# 131210_AriloRX_0_0.net
KiCad netlist of a schematic drawn in EAGLE
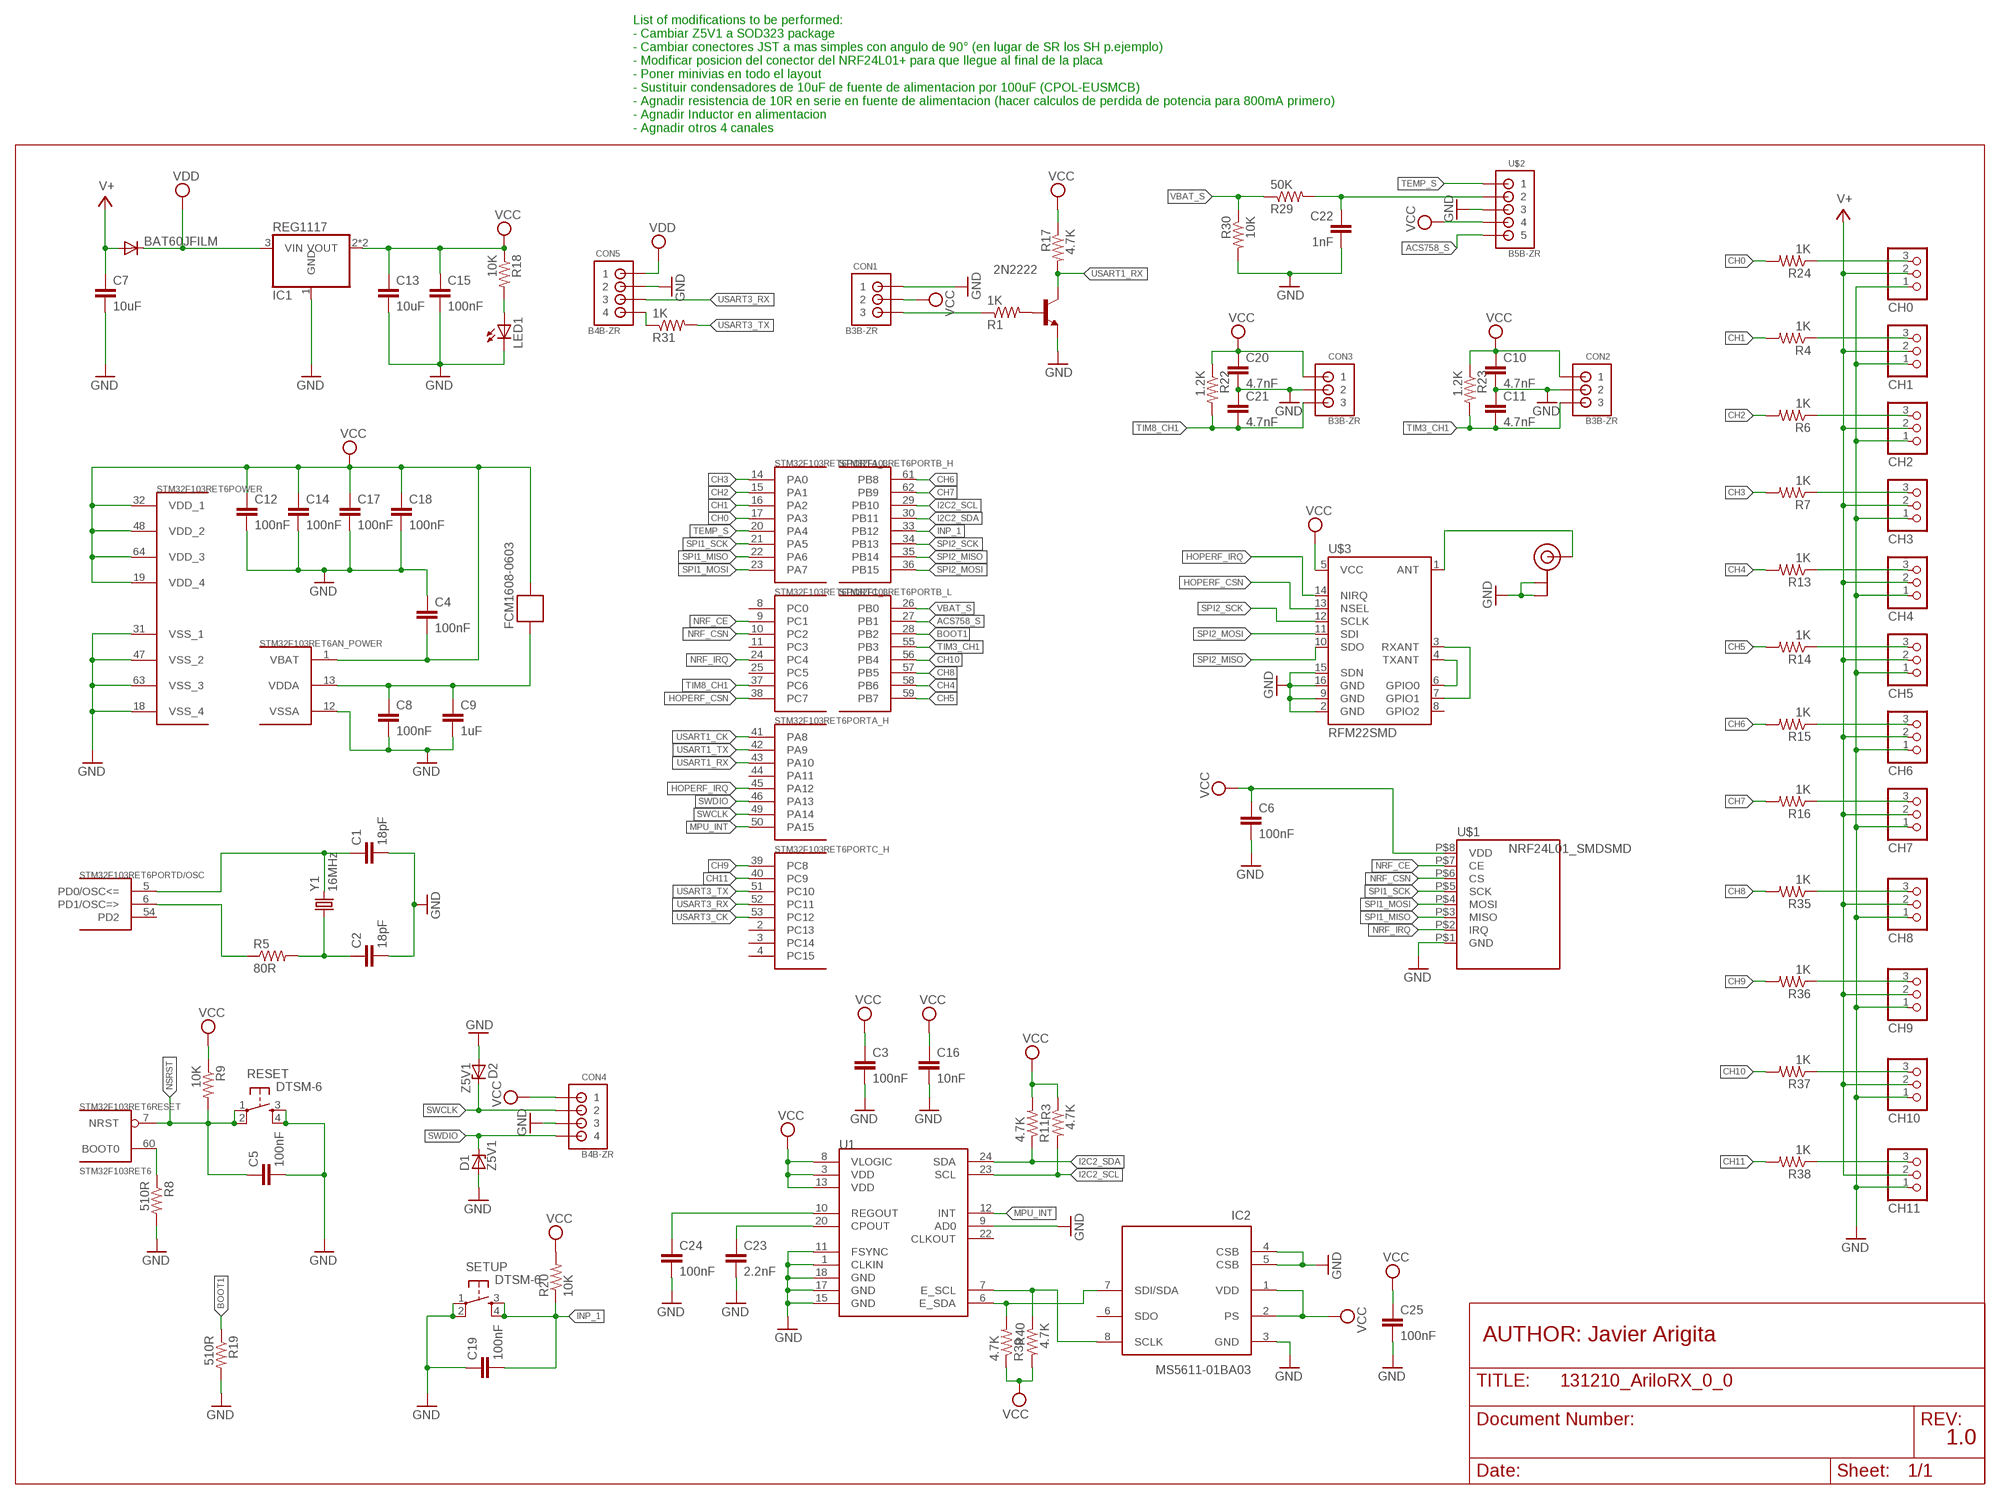
[diagram p0: schematic, sheet 1]

(export (version "E")
  (design (tool "Eeschema 10.0.6"))
  (components
    (comp (ref "2N2222")
      (value "MMBT2222ALT1-NPN-SOT23-BEC")
      (footprint "eagle-import:SOT23-BEC")
      (libsource (lib "eagle-import") (part "-NPN-SOT23-BECMMBT2222ALT1"))
    )
    (comp (ref "BAT60JFILM")
      (value "DIODE-SOD323-R")
      (footprint "eagle-import:SOD323-R")
      (libsource (lib "eagle-import") (part "DIODE-SOD323-R"))
    )
    (comp (ref "C1")
      (value "18pF")
      (footprint "eagle-import:C0805")
      (libsource (lib "eagle-import") (part "C-EUC0805"))
    )
    (comp (ref "C2")
      (value "18pF")
      (footprint "eagle-import:C0805")
      (libsource (lib "eagle-import") (part "C-EUC0805"))
    )
    (comp (ref "C3")
      (value "100nF")
      (footprint "eagle-import:C0805")
      (libsource (lib "eagle-import") (part "C-EUC0805"))
    )
    (comp (ref "C4")
      (value "100nF")
      (footprint "eagle-import:C0805")
      (libsource (lib "eagle-import") (part "C-EUC0805"))
    )
    (comp (ref "C5")
      (value "100nF")
      (footprint "eagle-import:C0805")
      (libsource (lib "eagle-import") (part "C-EUC0805"))
    )
    (comp (ref "C6")
      (value "100nF")
      (footprint "eagle-import:C0805")
      (libsource (lib "eagle-import") (part "C-EUC0805"))
    )
    (comp (ref "C7")
      (value "10uF")
      (footprint "eagle-import:C3216")
      (libsource (lib "eagle-import") (part "resistor_C-EUC3216"))
    )
    (comp (ref "C8")
      (value "100nF")
      (footprint "eagle-import:C0805")
      (libsource (lib "eagle-import") (part "C-EUC0805"))
    )
    (comp (ref "C9")
      (value "1uF")
      (footprint "eagle-import:C3216")
      (libsource (lib "eagle-import") (part "resistor_C-EUC3216"))
    )
    (comp (ref "C10")
      (value "4.7nF")
      (footprint "eagle-import:C0805")
      (libsource (lib "eagle-import") (part "C-EUC0805"))
    )
    (comp (ref "C11")
      (value "4.7nF")
      (footprint "eagle-import:C0805")
      (libsource (lib "eagle-import") (part "C-EUC0805"))
    )
    (comp (ref "C12")
      (value "100nF")
      (footprint "eagle-import:C0805")
      (libsource (lib "eagle-import") (part "C-EUC0805"))
    )
    (comp (ref "C13")
      (value "10uF")
      (footprint "eagle-import:C3216")
      (libsource (lib "eagle-import") (part "resistor_C-EUC3216"))
    )
    (comp (ref "C14")
      (value "100nF")
      (footprint "eagle-import:C0805")
      (libsource (lib "eagle-import") (part "C-EUC0805"))
    )
    (comp (ref "C15")
      (value "100nF")
      (footprint "eagle-import:C0805")
      (libsource (lib "eagle-import") (part "C-EUC0805"))
    )
    (comp (ref "C16")
      (value "10nF")
      (footprint "eagle-import:C0805")
      (libsource (lib "eagle-import") (part "C-EUC0805"))
    )
    (comp (ref "C17")
      (value "100nF")
      (footprint "eagle-import:C0805")
      (libsource (lib "eagle-import") (part "C-EUC0805"))
    )
    (comp (ref "C18")
      (value "100nF")
      (footprint "eagle-import:C0805")
      (libsource (lib "eagle-import") (part "C-EUC0805"))
    )
    (comp (ref "C19")
      (value "100nF")
      (footprint "eagle-import:C0805")
      (libsource (lib "eagle-import") (part "C-EUC0805"))
    )
    (comp (ref "C20")
      (value "4.7nF")
      (footprint "eagle-import:C0805")
      (libsource (lib "eagle-import") (part "C-EUC0805"))
    )
    (comp (ref "C21")
      (value "4.7nF")
      (footprint "eagle-import:C0805")
      (libsource (lib "eagle-import") (part "C-EUC0805"))
    )
    (comp (ref "C22")
      (value "1nF")
      (footprint "eagle-import:C0805")
      (libsource (lib "eagle-import") (part "C-EUC0805"))
    )
    (comp (ref "C23")
      (value "2.2nF")
      (footprint "eagle-import:C0805")
      (libsource (lib "eagle-import") (part "C-EUC0805"))
    )
    (comp (ref "C24")
      (value "100nF")
      (footprint "eagle-import:C0805")
      (libsource (lib "eagle-import") (part "C-EUC0805"))
    )
    (comp (ref "C25")
      (value "100nF")
      (footprint "eagle-import:C0805")
      (libsource (lib "eagle-import") (part "C-EUC0805"))
    )
    (comp (ref "CH0")
      (value "PINHD-1X3")
      (footprint "eagle-import:1X03")
      (libsource (lib "eagle-import") (part "PINHD-1X3"))
    )
    (comp (ref "CH1")
      (value "PINHD-1X3")
      (footprint "eagle-import:1X03")
      (libsource (lib "eagle-import") (part "PINHD-1X3"))
    )
    (comp (ref "CH2")
      (value "PINHD-1X3")
      (footprint "eagle-import:1X03")
      (libsource (lib "eagle-import") (part "PINHD-1X3"))
    )
    (comp (ref "CH3")
      (value "PINHD-1X3")
      (footprint "eagle-import:1X03")
      (libsource (lib "eagle-import") (part "PINHD-1X3"))
    )
    (comp (ref "CH4")
      (value "PINHD-1X3")
      (footprint "eagle-import:1X03")
      (libsource (lib "eagle-import") (part "PINHD-1X3"))
    )
    (comp (ref "CH5")
      (value "PINHD-1X3")
      (footprint "eagle-import:1X03")
      (libsource (lib "eagle-import") (part "PINHD-1X3"))
    )
    (comp (ref "CH6")
      (value "PINHD-1X3")
      (footprint "eagle-import:1X03")
      (libsource (lib "eagle-import") (part "PINHD-1X3"))
    )
    (comp (ref "CH7")
      (value "PINHD-1X3")
      (footprint "eagle-import:1X03")
      (libsource (lib "eagle-import") (part "PINHD-1X3"))
    )
    (comp (ref "CH8")
      (value "PINHD-1X3")
      (footprint "eagle-import:1X03")
      (libsource (lib "eagle-import") (part "PINHD-1X3"))
    )
    (comp (ref "CH9")
      (value "PINHD-1X3")
      (footprint "eagle-import:1X03")
      (libsource (lib "eagle-import") (part "PINHD-1X3"))
    )
    (comp (ref "CH10")
      (value "PINHD-1X3")
      (footprint "eagle-import:1X03")
      (libsource (lib "eagle-import") (part "PINHD-1X3"))
    )
    (comp (ref "CH11")
      (value "PINHD-1X3")
      (footprint "eagle-import:1X03")
      (libsource (lib "eagle-import") (part "PINHD-1X3"))
    )
    (comp (ref "CON1")
      (value "B3B-ZR")
      (footprint "eagle-import:B3B-ZR")
      (libsource (lib "eagle-import") (part "B3B-ZR"))
    )
    (comp (ref "CON2")
      (value "B3B-ZR")
      (footprint "eagle-import:B3B-ZR")
      (libsource (lib "eagle-import") (part "B3B-ZR"))
    )
    (comp (ref "CON3")
      (value "B3B-ZR")
      (footprint "eagle-import:B3B-ZR")
      (libsource (lib "eagle-import") (part "B3B-ZR"))
    )
    (comp (ref "CON4")
      (value "B4B-ZR")
      (footprint "eagle-import:B4B-ZR")
      (libsource (lib "eagle-import") (part "B4B-ZR"))
    )
    (comp (ref "CON5")
      (value "B4B-ZR")
      (footprint "eagle-import:B4B-ZR")
      (libsource (lib "eagle-import") (part "B4B-ZR"))
    )
    (comp (ref "D1")
      (value "Z5V1")
      (footprint "eagle-import:SOD80C")
      (libsource (lib "eagle-import") (part "ZENER-DIODESOD80C"))
    )
    (comp (ref "D2")
      (value "Z5V1")
      (footprint "eagle-import:SOD80C")
      (libsource (lib "eagle-import") (part "ZENER-DIODESOD80C"))
    )
    (comp (ref "FCM1608-0603")
      (value "FERRITE-BEAD")
      (footprint "eagle-import:R0603")
      (libsource (lib "eagle-import") (part "FERRITE-BEAD"))
    )
    (comp (ref "IC1")
      (value "REG1117")
      (footprint "eagle-import:SOT223")
      (libsource (lib "eagle-import") (part "REG1117"))
    )
    (comp (ref "IC2")
      (value "MS5611-01BA03")
      (footprint "eagle-import:SON125P300X500X100-8N")
      (libsource (lib "eagle-import") (part "MS5611-01BA03"))
    )
    (comp (ref "LED1")
      (value "LED0805")
      (footprint "eagle-import:CHIPLED_0805")
      (libsource (lib "eagle-import") (part "LED0805"))
    )
    (comp (ref "R1")
      (value "1K")
      (footprint "eagle-import:R0805")
      (libsource (lib "eagle-import") (part "RESISTOR0805"))
    )
    (comp (ref "R3")
      (value "4.7K")
      (footprint "eagle-import:R0805")
      (libsource (lib "eagle-import") (part "RESISTOR0805"))
    )
    (comp (ref "R4")
      (value "1K")
      (footprint "eagle-import:R0805")
      (libsource (lib "eagle-import") (part "RESISTOR0805"))
    )
    (comp (ref "R5")
      (value "80R")
      (footprint "eagle-import:R0805")
      (libsource (lib "eagle-import") (part "RESISTOR0805"))
    )
    (comp (ref "R6")
      (value "1K")
      (footprint "eagle-import:R0805")
      (libsource (lib "eagle-import") (part "RESISTOR0805"))
    )
    (comp (ref "R7")
      (value "1K")
      (footprint "eagle-import:R0805")
      (libsource (lib "eagle-import") (part "RESISTOR0805"))
    )
    (comp (ref "R8")
      (value "510R")
      (footprint "eagle-import:R0805")
      (libsource (lib "eagle-import") (part "RESISTOR0805"))
    )
    (comp (ref "R9")
      (value "10K")
      (footprint "eagle-import:R0805")
      (libsource (lib "eagle-import") (part "RESISTOR0805"))
    )
    (comp (ref "R11")
      (value "4.7K")
      (footprint "eagle-import:R0805")
      (libsource (lib "eagle-import") (part "RESISTOR0805"))
    )
    (comp (ref "R13")
      (value "1K")
      (footprint "eagle-import:R0805")
      (libsource (lib "eagle-import") (part "RESISTOR0805"))
    )
    (comp (ref "R14")
      (value "1K")
      (footprint "eagle-import:R0805")
      (libsource (lib "eagle-import") (part "RESISTOR0805"))
    )
    (comp (ref "R15")
      (value "1K")
      (footprint "eagle-import:R0805")
      (libsource (lib "eagle-import") (part "RESISTOR0805"))
    )
    (comp (ref "R16")
      (value "1K")
      (footprint "eagle-import:R0805")
      (libsource (lib "eagle-import") (part "RESISTOR0805"))
    )
    (comp (ref "R17")
      (value "4.7K")
      (footprint "eagle-import:R0805")
      (libsource (lib "eagle-import") (part "RESISTOR0805"))
    )
    (comp (ref "R18")
      (value "10K")
      (footprint "eagle-import:R0805")
      (libsource (lib "eagle-import") (part "RESISTOR0805"))
    )
    (comp (ref "R19")
      (value "510R")
      (footprint "eagle-import:R0805")
      (libsource (lib "eagle-import") (part "RESISTOR0805"))
    )
    (comp (ref "R20")
      (value "10K")
      (footprint "eagle-import:R0805")
      (libsource (lib "eagle-import") (part "RESISTOR0805"))
    )
    (comp (ref "R22")
      (value "1.2K")
      (footprint "eagle-import:R0805")
      (libsource (lib "eagle-import") (part "RESISTOR0805"))
    )
    (comp (ref "R23")
      (value "1.2K")
      (footprint "eagle-import:R0805")
      (libsource (lib "eagle-import") (part "RESISTOR0805"))
    )
    (comp (ref "R24")
      (value "1K")
      (footprint "eagle-import:R0805")
      (libsource (lib "eagle-import") (part "RESISTOR0805"))
    )
    (comp (ref "R29")
      (value "50K")
      (footprint "eagle-import:R0805")
      (libsource (lib "eagle-import") (part "RESISTOR0805"))
    )
    (comp (ref "R30")
      (value "10K")
      (footprint "eagle-import:R0805")
      (libsource (lib "eagle-import") (part "RESISTOR0805"))
    )
    (comp (ref "R31")
      (value "1K")
      (footprint "eagle-import:R0805")
      (libsource (lib "eagle-import") (part "RESISTOR0805"))
    )
    (comp (ref "R35")
      (value "1K")
      (footprint "eagle-import:R0805")
      (libsource (lib "eagle-import") (part "RESISTOR0805"))
    )
    (comp (ref "R36")
      (value "1K")
      (footprint "eagle-import:R0805")
      (libsource (lib "eagle-import") (part "RESISTOR0805"))
    )
    (comp (ref "R37")
      (value "1K")
      (footprint "eagle-import:R0805")
      (libsource (lib "eagle-import") (part "RESISTOR0805"))
    )
    (comp (ref "R38")
      (value "1K")
      (footprint "eagle-import:R0805")
      (libsource (lib "eagle-import") (part "RESISTOR0805"))
    )
    (comp (ref "R39")
      (value "4.7K")
      (footprint "eagle-import:R0805")
      (libsource (lib "eagle-import") (part "RESISTOR0805"))
    )
    (comp (ref "R40")
      (value "4.7K")
      (footprint "eagle-import:R0805")
      (libsource (lib "eagle-import") (part "RESISTOR0805"))
    )
    (comp (ref "RESET")
      (value "DTSM-6")
      (footprint "eagle-import:DTSM-6")
      (libsource (lib "eagle-import") (part "DTSM-6"))
    )
    (comp (ref "SETUP")
      (value "DTSM-6")
      (footprint "eagle-import:DTSM-6")
      (libsource (lib "eagle-import") (part "DTSM-6"))
    )
    (comp (ref "STM32F103RET6")
      (value "STM32F103RET6")
      (footprint "eagle-import:TQFP64")
      (libsource (lib "eagle-import") (part "STM32F10XRXT6"))
    )
    (comp (ref "U$1")
      (value "NRF24L01_SMDSMD")
      (footprint "eagle-import:NRF24L01_SMD")
      (libsource (lib "eagle-import") (part "NRF24L01_SMDSMD"))
    )
    (comp (ref "U$2")
      (value "B5B-ZR")
      (footprint "eagle-import:B5B-ZR")
      (libsource (lib "eagle-import") (part "B5B-ZR"))
    )
    (comp (ref "U$3")
      (value "RFM22SMD")
      (footprint "eagle-import:RFM22-XXX-S2")
      (libsource (lib "eagle-import") (part "RFM22SMD"))
    )
    (comp (ref "U$4")
      (value "U.FL")
      (footprint "eagle-import:U.FL")
      (libsource (lib "eagle-import") (part "U.FL"))
    )
    (comp (ref "U1")
      (value "MPU-9150QFN-24-NP")
      (footprint "eagle-import:QFN-24-NP")
      (libsource (lib "eagle-import") (part "MPU-9150QFN-24-NP"))
    )
    (comp (ref "Y1")
      (value "16MHz")
      (footprint "eagle-import:CRYSTAL-SMD-5X3")
      (libsource (lib "eagle-import") (part "CRYSTAL5X3"))
    )
  )
  (nets
    (net (code "1") (name "ACS758_S") (class "Default")
      (node (ref "STM32F103RET6") (pin "27") (pinfunction "PB1_27") (pintype "bidirectional"))
      (node (ref "U$2") (pin "5") (pinfunction "5_5") (pintype "bidirectional"))
    )
    (net (code "2") (name "BOOT1") (class "Default")
      (node (ref "R19") (pin "1") (pinfunction "1_1") (pintype "passive"))
      (node (ref "STM32F103RET6") (pin "28") (pinfunction "PB2_28") (pintype "bidirectional"))
    )
    (net (code "3") (name "CH0") (class "Default")
      (node (ref "R24") (pin "2") (pinfunction "2_2") (pintype "passive"))
      (node (ref "STM32F103RET6") (pin "17") (pinfunction "PA3_17") (pintype "bidirectional"))
    )
    (net (code "4") (name "CH1") (class "Default")
      (node (ref "R4") (pin "2") (pinfunction "2_2") (pintype "passive"))
      (node (ref "STM32F103RET6") (pin "16") (pinfunction "PA2_16") (pintype "bidirectional"))
    )
    (net (code "5") (name "CH2") (class "Default")
      (node (ref "R6") (pin "2") (pinfunction "2_2") (pintype "passive"))
      (node (ref "STM32F103RET6") (pin "15") (pinfunction "PA1_15") (pintype "bidirectional"))
    )
    (net (code "6") (name "CH3") (class "Default")
      (node (ref "R7") (pin "2") (pinfunction "2_2") (pintype "passive"))
      (node (ref "STM32F103RET6") (pin "14") (pinfunction "PA0_14") (pintype "bidirectional"))
    )
    (net (code "7") (name "CH4") (class "Default")
      (node (ref "R13") (pin "2") (pinfunction "2_2") (pintype "passive"))
      (node (ref "STM32F103RET6") (pin "58") (pinfunction "PB6_58") (pintype "bidirectional"))
    )
    (net (code "8") (name "CH5") (class "Default")
      (node (ref "R14") (pin "2") (pinfunction "2_2") (pintype "passive"))
      (node (ref "STM32F103RET6") (pin "59") (pinfunction "PB7_59") (pintype "bidirectional"))
    )
    (net (code "9") (name "CH6") (class "Default")
      (node (ref "R15") (pin "2") (pinfunction "2_2") (pintype "passive"))
      (node (ref "STM32F103RET6") (pin "61") (pinfunction "PB8_61") (pintype "bidirectional"))
    )
    (net (code "10") (name "CH7") (class "Default")
      (node (ref "R16") (pin "2") (pinfunction "2_2") (pintype "passive"))
      (node (ref "STM32F103RET6") (pin "62") (pinfunction "PB9_62") (pintype "bidirectional"))
    )
    (net (code "11") (name "CH8") (class "Default")
      (node (ref "R35") (pin "2") (pinfunction "2_2") (pintype "passive"))
      (node (ref "STM32F103RET6") (pin "57") (pinfunction "PB5_57") (pintype "bidirectional"))
    )
    (net (code "12") (name "CH9") (class "Default")
      (node (ref "R36") (pin "2") (pinfunction "2_2") (pintype "passive"))
      (node (ref "STM32F103RET6") (pin "39") (pinfunction "PC8_39") (pintype "bidirectional"))
    )
    (net (code "13") (name "CH10") (class "Default")
      (node (ref "R37") (pin "2") (pinfunction "2_2") (pintype "passive"))
      (node (ref "STM32F103RET6") (pin "56") (pinfunction "PB4_56") (pintype "bidirectional"))
    )
    (net (code "14") (name "CH11") (class "Default")
      (node (ref "R38") (pin "2") (pinfunction "2_2") (pintype "passive"))
      (node (ref "STM32F103RET6") (pin "40") (pinfunction "PC9_40") (pintype "bidirectional"))
    )
    (net (code "15") (name "GND") (class "Default")
      (node (ref "2N2222") (pin "E") (pinfunction "E_E") (pintype "passive"))
      (node (ref "C1") (pin "2") (pinfunction "2_2") (pintype "passive"))
      (node (ref "C10") (pin "2") (pinfunction "2_2") (pintype "passive"))
      (node (ref "C11") (pin "1") (pinfunction "1_1") (pintype "passive"))
      (node (ref "C12") (pin "2") (pinfunction "2_2") (pintype "passive"))
      (node (ref "C13") (pin "2") (pinfunction "2_2") (pintype "passive"))
      (node (ref "C14") (pin "2") (pinfunction "2_2") (pintype "passive"))
      (node (ref "C15") (pin "2") (pinfunction "2_2") (pintype "passive"))
      (node (ref "C16") (pin "2") (pinfunction "2_2") (pintype "passive"))
      (node (ref "C17") (pin "2") (pinfunction "2_2") (pintype "passive"))
      (node (ref "C18") (pin "2") (pinfunction "2_2") (pintype "passive"))
      (node (ref "C19") (pin "1") (pinfunction "1_1") (pintype "passive"))
      (node (ref "C2") (pin "2") (pinfunction "2_2") (pintype "passive"))
      (node (ref "C20") (pin "2") (pinfunction "2_2") (pintype "passive"))
      (node (ref "C21") (pin "1") (pinfunction "1_1") (pintype "passive"))
      (node (ref "C22") (pin "2") (pinfunction "2_2") (pintype "passive"))
      (node (ref "C23") (pin "2") (pinfunction "2_2") (pintype "passive"))
      (node (ref "C24") (pin "2") (pinfunction "2_2") (pintype "passive"))
      (node (ref "C25") (pin "2") (pinfunction "2_2") (pintype "passive"))
      (node (ref "C3") (pin "2") (pinfunction "2_2") (pintype "passive"))
      (node (ref "C4") (pin "1") (pinfunction "1_1") (pintype "passive"))
      (node (ref "C5") (pin "2") (pinfunction "2_2") (pintype "passive"))
      (node (ref "C6") (pin "2") (pinfunction "2_2") (pintype "passive"))
      (node (ref "C7") (pin "2") (pinfunction "2_2") (pintype "passive"))
      (node (ref "C8") (pin "2") (pinfunction "2_2") (pintype "passive"))
      (node (ref "C9") (pin "2") (pinfunction "2_2") (pintype "passive"))
      (node (ref "CH0") (pin "1") (pinfunction "1_1") (pintype "passive"))
      (node (ref "CH1") (pin "1") (pinfunction "1_1") (pintype "passive"))
      (node (ref "CH10") (pin "1") (pinfunction "1_1") (pintype "passive"))
      (node (ref "CH11") (pin "1") (pinfunction "1_1") (pintype "passive"))
      (node (ref "CH2") (pin "1") (pinfunction "1_1") (pintype "passive"))
      (node (ref "CH3") (pin "1") (pinfunction "1_1") (pintype "passive"))
      (node (ref "CH4") (pin "1") (pinfunction "1_1") (pintype "passive"))
      (node (ref "CH5") (pin "1") (pinfunction "1_1") (pintype "passive"))
      (node (ref "CH6") (pin "1") (pinfunction "1_1") (pintype "passive"))
      (node (ref "CH7") (pin "1") (pinfunction "1_1") (pintype "passive"))
      (node (ref "CH8") (pin "1") (pinfunction "1_1") (pintype "passive"))
      (node (ref "CH9") (pin "1") (pinfunction "1_1") (pintype "passive"))
      (node (ref "CON1") (pin "1") (pinfunction "1_1") (pintype "bidirectional"))
      (node (ref "CON2") (pin "2") (pinfunction "2_2") (pintype "bidirectional"))
      (node (ref "CON3") (pin "2") (pinfunction "2_2") (pintype "bidirectional"))
      (node (ref "CON4") (pin "3") (pinfunction "3_3") (pintype "bidirectional"))
      (node (ref "CON5") (pin "2") (pinfunction "2_2") (pintype "bidirectional"))
      (node (ref "D1") (pin "A") (pinfunction "A_A") (pintype "passive"))
      (node (ref "D2") (pin "A") (pinfunction "A_A") (pintype "passive"))
      (node (ref "IC1") (pin "1") (pinfunction "GND_1") (pintype "power_in"))
      (node (ref "IC2") (pin "3") (pinfunction "GND_3") (pintype "power_in"))
      (node (ref "IC2") (pin "4") (pinfunction "CSB_4") (pintype "input"))
      (node (ref "IC2") (pin "5") (pinfunction "CSB_5") (pintype "input"))
      (node (ref "LED1") (pin "C") (pinfunction "C_C") (pintype "passive"))
      (node (ref "R19") (pin "2") (pinfunction "2_2") (pintype "passive"))
      (node (ref "R30") (pin "2") (pinfunction "2_2") (pintype "passive"))
      (node (ref "R8") (pin "2") (pinfunction "2_2") (pintype "passive"))
      (node (ref "RESET") (pin "3") (pinfunction "3_3") (pintype "passive"))
      (node (ref "RESET") (pin "4") (pinfunction "4_4") (pintype "passive"))
      (node (ref "SETUP") (pin "1") (pinfunction "1_1") (pintype "passive"))
      (node (ref "SETUP") (pin "2") (pinfunction "2_2") (pintype "passive"))
      (node (ref "STM32F103RET6") (pin "12") (pinfunction "VSSA_12") (pintype "power_in"))
      (node (ref "STM32F103RET6") (pin "18") (pinfunction "VSS_4_18") (pintype "power_in"))
      (node (ref "STM32F103RET6") (pin "31") (pinfunction "VSS_1_31") (pintype "power_in"))
      (node (ref "STM32F103RET6") (pin "47") (pinfunction "VSS_2_47") (pintype "power_in"))
      (node (ref "STM32F103RET6") (pin "63") (pinfunction "VSS_3_63") (pintype "power_in"))
      (node (ref "U$1") (pin "P$1") (pinfunction "GND_P$1") (pintype "power_in"))
      (node (ref "U$2") (pin "3") (pinfunction "3_3") (pintype "bidirectional"))
      (node (ref "U$3") (pin "15") (pinfunction "SDN_15") (pintype "input"))
      (node (ref "U$3") (pin "16") (pinfunction "GND_16") (pintype "power_in"))
      (node (ref "U$3") (pin "2") (pinfunction "GND_2") (pintype "power_in"))
      (node (ref "U$3") (pin "9") (pinfunction "GND_9") (pintype "power_in"))
      (node (ref "U$4") (pin "P$1") (pinfunction "GND_P$1") (pintype "bidirectional"))
      (node (ref "U$4") (pin "P$2") (pinfunction "GND_P$2") (pintype "bidirectional"))
      (node (ref "U1") (pin "1") (pinfunction "CLKIN_1") (pintype "bidirectional"))
      (node (ref "U1") (pin "11") (pinfunction "FSYNC_11") (pintype "bidirectional"))
      (node (ref "U1") (pin "15") (pinfunction "GND_15") (pintype "bidirectional"))
      (node (ref "U1") (pin "17") (pinfunction "GND_17") (pintype "bidirectional"))
      (node (ref "U1") (pin "18") (pinfunction "GND_18") (pintype "bidirectional"))
      (node (ref "U1") (pin "9") (pinfunction "AD0_9") (pintype "bidirectional"))
    )
    (net (code "16") (name "HOPERF_CSN") (class "Default")
      (node (ref "STM32F103RET6") (pin "38") (pinfunction "PC7_38") (pintype "bidirectional"))
      (node (ref "U$3") (pin "13") (pinfunction "NSEL_13") (pintype "input"))
    )
    (net (code "17") (name "HOPERF_IRQ") (class "Default")
      (node (ref "STM32F103RET6") (pin "45") (pinfunction "PA12_45") (pintype "bidirectional"))
      (node (ref "U$3") (pin "14") (pinfunction "NIRQ_14") (pintype "output"))
    )
    (net (code "18") (name "I2C2_SCL") (class "Default")
      (node (ref "R3") (pin "2") (pinfunction "2_2") (pintype "passive"))
      (node (ref "STM32F103RET6") (pin "29") (pinfunction "PB10_29") (pintype "bidirectional"))
      (node (ref "U1") (pin "23") (pinfunction "SCL_23") (pintype "bidirectional"))
    )
    (net (code "19") (name "I2C2_SDA") (class "Default")
      (node (ref "R11") (pin "1") (pinfunction "1_1") (pintype "passive"))
      (node (ref "STM32F103RET6") (pin "30") (pinfunction "PB11_30") (pintype "bidirectional"))
      (node (ref "U1") (pin "24") (pinfunction "SDA_24") (pintype "bidirectional"))
    )
    (net (code "20") (name "INP_1") (class "Default")
      (node (ref "C19") (pin "2") (pinfunction "2_2") (pintype "passive"))
      (node (ref "R20") (pin "1") (pinfunction "1_1") (pintype "passive"))
      (node (ref "SETUP") (pin "3") (pinfunction "3_3") (pintype "passive"))
      (node (ref "SETUP") (pin "4") (pinfunction "4_4") (pintype "passive"))
      (node (ref "STM32F103RET6") (pin "33") (pinfunction "PB12_33") (pintype "bidirectional"))
    )
    (net (code "21") (name "MPU_INT") (class "Default")
      (node (ref "STM32F103RET6") (pin "50") (pinfunction "PA15_50") (pintype "bidirectional"))
      (node (ref "U1") (pin "12") (pinfunction "INT_12") (pintype "bidirectional"))
    )
    (net (code "22") (name "NRF_CE") (class "Default")
      (node (ref "STM32F103RET6") (pin "9") (pinfunction "PC1_9") (pintype "bidirectional"))
      (node (ref "U$1") (pin "P$7") (pinfunction "CE_P$7") (pintype "input"))
    )
    (net (code "23") (name "NRF_CSN") (class "Default")
      (node (ref "STM32F103RET6") (pin "10") (pinfunction "PC2_10") (pintype "bidirectional"))
      (node (ref "U$1") (pin "P$6") (pinfunction "CS_P$6") (pintype "input"))
    )
    (net (code "24") (name "NRF_IRQ") (class "Default")
      (node (ref "STM32F103RET6") (pin "24") (pinfunction "PC4_24") (pintype "bidirectional"))
      (node (ref "U$1") (pin "P$2") (pinfunction "IRQ_P$2") (pintype "output"))
    )
    (net (code "25") (name "NSRST") (class "Default")
      (node (ref "C5") (pin "1") (pinfunction "1_1") (pintype "passive"))
      (node (ref "R9") (pin "2") (pinfunction "2_2") (pintype "passive"))
      (node (ref "RESET") (pin "1") (pinfunction "1_1") (pintype "passive"))
      (node (ref "RESET") (pin "2") (pinfunction "2_2") (pintype "passive"))
      (node (ref "STM32F103RET6") (pin "7") (pinfunction "NRST_7") (pintype "input"))
    )
    (net (code "26") (name "Net-(2N2222-PadB)") (class "Default")
      (node (ref "2N2222") (pin "B") (pinfunction "B_B") (pintype "passive"))
      (node (ref "R1") (pin "2") (pinfunction "2_2") (pintype "passive"))
    )
    (net (code "27") (name "Net-(C2-Pad1)") (class "Default")
      (node (ref "C2") (pin "1") (pinfunction "1_1") (pintype "passive"))
      (node (ref "R5") (pin "2") (pinfunction "2_2") (pintype "passive"))
      (node (ref "Y1") (pin "1") (pinfunction "1_1") (pintype "passive"))
    )
    (net (code "28") (name "Net-(C22-Pad1)") (class "Default")
      (node (ref "C22") (pin "1") (pinfunction "1_1") (pintype "passive"))
      (node (ref "R29") (pin "2") (pinfunction "2_2") (pintype "passive"))
      (node (ref "U$2") (pin "2") (pinfunction "2_2") (pintype "bidirectional"))
    )
    (net (code "29") (name "Net-(CH0-Pad3)") (class "Default")
      (node (ref "CH0") (pin "3") (pinfunction "3_3") (pintype "passive"))
      (node (ref "R24") (pin "1") (pinfunction "1_1") (pintype "passive"))
    )
    (net (code "30") (name "Net-(CH1-Pad3)") (class "Default")
      (node (ref "CH1") (pin "3") (pinfunction "3_3") (pintype "passive"))
      (node (ref "R4") (pin "1") (pinfunction "1_1") (pintype "passive"))
    )
    (net (code "31") (name "Net-(CH2-Pad3)") (class "Default")
      (node (ref "CH2") (pin "3") (pinfunction "3_3") (pintype "passive"))
      (node (ref "R6") (pin "1") (pinfunction "1_1") (pintype "passive"))
    )
    (net (code "32") (name "Net-(CH3-Pad3)") (class "Default")
      (node (ref "CH3") (pin "3") (pinfunction "3_3") (pintype "passive"))
      (node (ref "R7") (pin "1") (pinfunction "1_1") (pintype "passive"))
    )
    (net (code "33") (name "Net-(CH4-Pad3)") (class "Default")
      (node (ref "CH4") (pin "3") (pinfunction "3_3") (pintype "passive"))
      (node (ref "R13") (pin "1") (pinfunction "1_1") (pintype "passive"))
    )
    (net (code "34") (name "Net-(CH5-Pad3)") (class "Default")
      (node (ref "CH5") (pin "3") (pinfunction "3_3") (pintype "passive"))
      (node (ref "R14") (pin "1") (pinfunction "1_1") (pintype "passive"))
    )
    (net (code "35") (name "Net-(CH6-Pad3)") (class "Default")
      (node (ref "CH6") (pin "3") (pinfunction "3_3") (pintype "passive"))
      (node (ref "R15") (pin "1") (pinfunction "1_1") (pintype "passive"))
    )
    (net (code "36") (name "Net-(CH7-Pad3)") (class "Default")
      (node (ref "CH7") (pin "3") (pinfunction "3_3") (pintype "passive"))
      (node (ref "R16") (pin "1") (pinfunction "1_1") (pintype "passive"))
    )
    (net (code "37") (name "Net-(CH8-Pad3)") (class "Default")
      (node (ref "CH8") (pin "3") (pinfunction "3_3") (pintype "passive"))
      (node (ref "R35") (pin "1") (pinfunction "1_1") (pintype "passive"))
    )
    (net (code "38") (name "Net-(CH9-Pad3)") (class "Default")
      (node (ref "CH9") (pin "3") (pinfunction "3_3") (pintype "passive"))
      (node (ref "R36") (pin "1") (pinfunction "1_1") (pintype "passive"))
    )
    (net (code "39") (name "Net-(CH10-Pad3)") (class "Default")
      (node (ref "CH10") (pin "3") (pinfunction "3_3") (pintype "passive"))
      (node (ref "R37") (pin "1") (pinfunction "1_1") (pintype "passive"))
    )
    (net (code "40") (name "Net-(CH11-Pad3)") (class "Default")
      (node (ref "CH11") (pin "3") (pinfunction "3_3") (pintype "passive"))
      (node (ref "R38") (pin "1") (pinfunction "1_1") (pintype "passive"))
    )
    (net (code "41") (name "Net-(CON1-Pad3)") (class "Default")
      (node (ref "CON1") (pin "3") (pinfunction "3_3") (pintype "bidirectional"))
      (node (ref "R1") (pin "1") (pinfunction "1_1") (pintype "passive"))
    )
    (net (code "42") (name "Net-(CON5-Pad4)") (class "Default")
      (node (ref "CON5") (pin "4") (pinfunction "4_4") (pintype "bidirectional"))
      (node (ref "R31") (pin "1") (pinfunction "1_1") (pintype "passive"))
    )
    (net (code "43") (name "Net-(FCM1608-0603-P$2)") (class "Default")
      (node (ref "C8") (pin "1") (pinfunction "1_1") (pintype "passive"))
      (node (ref "C9") (pin "1") (pinfunction "1_1") (pintype "passive"))
      (node (ref "FCM1608-0603") (pin "2") (pinfunction "P$2_2") (pintype "bidirectional"))
      (node (ref "STM32F103RET6") (pin "13") (pinfunction "VDDA_13") (pintype "power_in"))
    )
    (net (code "44") (name "Net-(IC2-SCLK)") (class "Default")
      (node (ref "IC2") (pin "8") (pinfunction "SCLK_8") (pintype "input"))
      (node (ref "R40") (pin "1") (pinfunction "1_1") (pintype "passive"))
      (node (ref "U1") (pin "7") (pinfunction "E_SCL_7") (pintype "bidirectional"))
    )
    (net (code "45") (name "Net-(IC2-SDI{slash}SDA)") (class "Default")
      (node (ref "IC2") (pin "7") (pinfunction "SDI/SDA_7") (pintype "bidirectional"))
      (node (ref "R39") (pin "2") (pinfunction "2_2") (pintype "passive"))
      (node (ref "U1") (pin "6") (pinfunction "E_SDA_6") (pintype "bidirectional"))
    )
    (net (code "46") (name "Net-(LED1-PadA)") (class "Default")
      (node (ref "LED1") (pin "A") (pinfunction "A_A") (pintype "passive"))
      (node (ref "R18") (pin "2") (pinfunction "2_2") (pintype "passive"))
    )
    (net (code "47") (name "Net-(STM32F103RET6H-PD0{slash}OSC<=)") (class "Default")
      (node (ref "C1") (pin "1") (pinfunction "1_1") (pintype "passive"))
      (node (ref "STM32F103RET6") (pin "5") (pinfunction "PD0/OSC<=_5") (pintype "bidirectional"))
      (node (ref "Y1") (pin "3") (pinfunction "2_3") (pintype "passive"))
    )
    (net (code "48") (name "Net-(STM32F103RET6H-PD1{slash}OSC=>)") (class "Default")
      (node (ref "R5") (pin "1") (pinfunction "1_1") (pintype "passive"))
      (node (ref "STM32F103RET6") (pin "6") (pinfunction "PD1/OSC=>_6") (pintype "bidirectional"))
    )
    (net (code "49") (name "Net-(STM32F103RET6J-BOOT0)") (class "Default")
      (node (ref "R8") (pin "1") (pinfunction "1_1") (pintype "passive"))
      (node (ref "STM32F103RET6") (pin "60") (pinfunction "BOOT0_60") (pintype "input"))
    )
    (net (code "50") (name "Net-(U$3-ANT)") (class "Default")
      (node (ref "U$3") (pin "1") (pinfunction "ANT_1") (pintype "bidirectional"))
      (node (ref "U$4") (pin "P$3") (pinfunction "SIGNAL_P$3") (pintype "bidirectional"))
    )
    (net (code "51") (name "Net-(U$3-GPIO0)") (class "Default")
      (node (ref "U$3") (pin "4") (pinfunction "TXANT_4") (pintype "input"))
      (node (ref "U$3") (pin "6") (pinfunction "GPIO0_6") (pintype "bidirectional"))
    )
    (net (code "52") (name "Net-(U$3-GPIO1)") (class "Default")
      (node (ref "U$3") (pin "3") (pinfunction "RXANT_3") (pintype "input"))
      (node (ref "U$3") (pin "7") (pinfunction "GPIO1_7") (pintype "bidirectional"))
    )
    (net (code "53") (name "Net-(U1-CPOUT)") (class "Default")
      (node (ref "C23") (pin "1") (pinfunction "1_1") (pintype "passive"))
      (node (ref "U1") (pin "20") (pinfunction "CPOUT_20") (pintype "bidirectional"))
    )
    (net (code "54") (name "Net-(U1-REGOUT)") (class "Default")
      (node (ref "C24") (pin "1") (pinfunction "1_1") (pintype "passive"))
      (node (ref "U1") (pin "10") (pinfunction "REGOUT_10") (pintype "bidirectional"))
    )
    (net (code "55") (name "SPI1_MISO") (class "Default")
      (node (ref "STM32F103RET6") (pin "22") (pinfunction "PA6_22") (pintype "bidirectional"))
      (node (ref "U$1") (pin "P$3") (pinfunction "MISO_P$3") (pintype "output"))
    )
    (net (code "56") (name "SPI1_MOSI") (class "Default")
      (node (ref "STM32F103RET6") (pin "23") (pinfunction "PA7_23") (pintype "bidirectional"))
      (node (ref "U$1") (pin "P$4") (pinfunction "MOSI_P$4") (pintype "input"))
    )
    (net (code "57") (name "SPI1_SCK") (class "Default")
      (node (ref "STM32F103RET6") (pin "21") (pinfunction "PA5_21") (pintype "bidirectional"))
      (node (ref "U$1") (pin "P$5") (pinfunction "SCK_P$5") (pintype "input"))
    )
    (net (code "58") (name "SPI2_MISO") (class "Default")
      (node (ref "STM32F103RET6") (pin "35") (pinfunction "PB14_35") (pintype "bidirectional"))
      (node (ref "U$3") (pin "10") (pinfunction "SDO_10") (pintype "output"))
    )
    (net (code "59") (name "SPI2_MOSI") (class "Default")
      (node (ref "STM32F103RET6") (pin "36") (pinfunction "PB15_36") (pintype "bidirectional"))
      (node (ref "U$3") (pin "11") (pinfunction "SDI_11") (pintype "input"))
    )
    (net (code "60") (name "SPI2_SCK") (class "Default")
      (node (ref "STM32F103RET6") (pin "34") (pinfunction "PB13_34") (pintype "bidirectional"))
      (node (ref "U$3") (pin "12") (pinfunction "SCLK_12") (pintype "input"))
    )
    (net (code "61") (name "SWCLK") (class "Default")
      (node (ref "CON4") (pin "2") (pinfunction "2_2") (pintype "bidirectional"))
      (node (ref "D2") (pin "C") (pinfunction "C_C") (pintype "passive"))
      (node (ref "STM32F103RET6") (pin "49") (pinfunction "PA14_49") (pintype "bidirectional"))
    )
    (net (code "62") (name "SWDIO") (class "Default")
      (node (ref "CON4") (pin "4") (pinfunction "4_4") (pintype "bidirectional"))
      (node (ref "D1") (pin "C") (pinfunction "C_C") (pintype "passive"))
      (node (ref "STM32F103RET6") (pin "46") (pinfunction "PA13_46") (pintype "bidirectional"))
    )
    (net (code "63") (name "TEMP_S") (class "Default")
      (node (ref "STM32F103RET6") (pin "20") (pinfunction "PA4_20") (pintype "bidirectional"))
      (node (ref "U$2") (pin "1") (pinfunction "1_1") (pintype "bidirectional"))
    )
    (net (code "64") (name "TIM3_CH1") (class "Default")
      (node (ref "C11") (pin "2") (pinfunction "2_2") (pintype "passive"))
      (node (ref "CON2") (pin "3") (pinfunction "3_3") (pintype "bidirectional"))
      (node (ref "R23") (pin "2") (pinfunction "2_2") (pintype "passive"))
      (node (ref "STM32F103RET6") (pin "55") (pinfunction "PB3_55") (pintype "bidirectional"))
    )
    (net (code "65") (name "TIM8_CH1") (class "Default")
      (node (ref "C21") (pin "2") (pinfunction "2_2") (pintype "passive"))
      (node (ref "CON3") (pin "3") (pinfunction "3_3") (pintype "bidirectional"))
      (node (ref "R22") (pin "2") (pinfunction "2_2") (pintype "passive"))
      (node (ref "STM32F103RET6") (pin "37") (pinfunction "PC6_37") (pintype "bidirectional"))
    )
    (net (code "66") (name "USART1_CK") (class "Default")
      (node (ref "STM32F103RET6") (pin "41") (pinfunction "PA8_41") (pintype "bidirectional"))
    )
    (net (code "67") (name "USART1_RX") (class "Default")
      (node (ref "2N2222") (pin "C") (pinfunction "C_C") (pintype "passive"))
      (node (ref "R17") (pin "2") (pinfunction "2_2") (pintype "passive"))
      (node (ref "STM32F103RET6") (pin "43") (pinfunction "PA10_43") (pintype "bidirectional"))
    )
    (net (code "68") (name "USART1_TX") (class "Default")
      (node (ref "STM32F103RET6") (pin "42") (pinfunction "PA9_42") (pintype "bidirectional"))
    )
    (net (code "69") (name "USART3_CK") (class "Default")
      (node (ref "STM32F103RET6") (pin "53") (pinfunction "PC12_53") (pintype "bidirectional"))
    )
    (net (code "70") (name "USART3_RX") (class "Default")
      (node (ref "CON5") (pin "3") (pinfunction "3_3") (pintype "bidirectional"))
      (node (ref "STM32F103RET6") (pin "52") (pinfunction "PC11_52") (pintype "bidirectional"))
    )
    (net (code "71") (name "USART3_TX") (class "Default")
      (node (ref "R31") (pin "2") (pinfunction "2_2") (pintype "passive"))
      (node (ref "STM32F103RET6") (pin "51") (pinfunction "PC10_51") (pintype "bidirectional"))
    )
    (net (code "72") (name "V+") (class "Default")
      (node (ref "BAT60JFILM") (pin "A") (pinfunction "A_A") (pintype "passive"))
      (node (ref "C7") (pin "1") (pinfunction "1_1") (pintype "passive"))
      (node (ref "CH0") (pin "2") (pinfunction "2_2") (pintype "passive"))
      (node (ref "CH1") (pin "2") (pinfunction "2_2") (pintype "passive"))
      (node (ref "CH10") (pin "2") (pinfunction "2_2") (pintype "passive"))
      (node (ref "CH11") (pin "2") (pinfunction "2_2") (pintype "passive"))
      (node (ref "CH2") (pin "2") (pinfunction "2_2") (pintype "passive"))
      (node (ref "CH3") (pin "2") (pinfunction "2_2") (pintype "passive"))
      (node (ref "CH4") (pin "2") (pinfunction "2_2") (pintype "passive"))
      (node (ref "CH5") (pin "2") (pinfunction "2_2") (pintype "passive"))
      (node (ref "CH6") (pin "2") (pinfunction "2_2") (pintype "passive"))
      (node (ref "CH7") (pin "2") (pinfunction "2_2") (pintype "passive"))
      (node (ref "CH8") (pin "2") (pinfunction "2_2") (pintype "passive"))
      (node (ref "CH9") (pin "2") (pinfunction "2_2") (pintype "passive"))
    )
    (net (code "73") (name "VBAT_S") (class "Default")
      (node (ref "R29") (pin "1") (pinfunction "1_1") (pintype "passive"))
      (node (ref "R30") (pin "1") (pinfunction "1_1") (pintype "passive"))
      (node (ref "STM32F103RET6") (pin "26") (pinfunction "PB0_26") (pintype "bidirectional"))
    )
    (net (code "74") (name "VCC") (class "Default")
      (node (ref "C10") (pin "1") (pinfunction "1_1") (pintype "passive"))
      (node (ref "C12") (pin "1") (pinfunction "1_1") (pintype "passive"))
      (node (ref "C13") (pin "1") (pinfunction "1_1") (pintype "passive"))
      (node (ref "C14") (pin "1") (pinfunction "1_1") (pintype "passive"))
      (node (ref "C15") (pin "1") (pinfunction "1_1") (pintype "passive"))
      (node (ref "C16") (pin "1") (pinfunction "1_1") (pintype "passive"))
      (node (ref "C17") (pin "1") (pinfunction "1_1") (pintype "passive"))
      (node (ref "C18") (pin "1") (pinfunction "1_1") (pintype "passive"))
      (node (ref "C20") (pin "1") (pinfunction "1_1") (pintype "passive"))
      (node (ref "C25") (pin "1") (pinfunction "1_1") (pintype "passive"))
      (node (ref "C3") (pin "1") (pinfunction "1_1") (pintype "passive"))
      (node (ref "C4") (pin "2") (pinfunction "2_2") (pintype "passive"))
      (node (ref "C6") (pin "1") (pinfunction "1_1") (pintype "passive"))
      (node (ref "CON1") (pin "2") (pinfunction "2_2") (pintype "bidirectional"))
      (node (ref "CON2") (pin "1") (pinfunction "1_1") (pintype "bidirectional"))
      (node (ref "CON3") (pin "1") (pinfunction "1_1") (pintype "bidirectional"))
      (node (ref "CON4") (pin "1") (pinfunction "1_1") (pintype "bidirectional"))
      (node (ref "FCM1608-0603") (pin "1") (pinfunction "P$1_1") (pintype "bidirectional"))
      (node (ref "IC1") (pin "2") (pinfunction "VOUT_2") (pintype "power_in"))
      (node (ref "IC1") (pin "4") (pinfunction "VOUT_4") (pintype "power_in"))
      (node (ref "IC2") (pin "1") (pinfunction "VDD_1") (pintype "power_in"))
      (node (ref "IC2") (pin "2") (pinfunction "PS_2") (pintype "input"))
      (node (ref "R11") (pin "2") (pinfunction "2_2") (pintype "passive"))
      (node (ref "R17") (pin "1") (pinfunction "1_1") (pintype "passive"))
      (node (ref "R18") (pin "1") (pinfunction "1_1") (pintype "passive"))
      (node (ref "R20") (pin "2") (pinfunction "2_2") (pintype "passive"))
      (node (ref "R22") (pin "1") (pinfunction "1_1") (pintype "passive"))
      (node (ref "R23") (pin "1") (pinfunction "1_1") (pintype "passive"))
      (node (ref "R3") (pin "1") (pinfunction "1_1") (pintype "passive"))
      (node (ref "R39") (pin "1") (pinfunction "1_1") (pintype "passive"))
      (node (ref "R40") (pin "2") (pinfunction "2_2") (pintype "passive"))
      (node (ref "R9") (pin "1") (pinfunction "1_1") (pintype "passive"))
      (node (ref "STM32F103RET6") (pin "1") (pinfunction "VBAT_1") (pintype "power_in"))
      (node (ref "STM32F103RET6") (pin "19") (pinfunction "VDD_4_19") (pintype "power_in"))
      (node (ref "STM32F103RET6") (pin "32") (pinfunction "VDD_1_32") (pintype "power_in"))
      (node (ref "STM32F103RET6") (pin "48") (pinfunction "VDD_2_48") (pintype "power_in"))
      (node (ref "STM32F103RET6") (pin "64") (pinfunction "VDD_3_64") (pintype "power_in"))
      (node (ref "U$1") (pin "P$8") (pinfunction "VDD_P$8") (pintype "bidirectional"))
      (node (ref "U$2") (pin "4") (pinfunction "4_4") (pintype "bidirectional"))
      (node (ref "U$3") (pin "5") (pinfunction "VCC_5") (pintype "bidirectional"))
      (node (ref "U1") (pin "13") (pinfunction "VDD_13") (pintype "bidirectional"))
      (node (ref "U1") (pin "3") (pinfunction "VDD_3") (pintype "bidirectional"))
      (node (ref "U1") (pin "8") (pinfunction "VLOGIC_8") (pintype "bidirectional"))
    )
    (net (code "75") (name "VDD") (class "Default")
      (node (ref "BAT60JFILM") (pin "C") (pinfunction "C_C") (pintype "passive"))
      (node (ref "CON5") (pin "1") (pinfunction "1_1") (pintype "bidirectional"))
      (node (ref "IC1") (pin "3") (pinfunction "VIN_3") (pintype "input"))
    )
    (net (code "76") (name "unconnected-(IC2-SDO-Pad6)") (class "Default")
      (node (ref "IC2") (pin "6") (pinfunction "SDO_6") (pintype "output"))
    )
    (net (code "77") (name "unconnected-(STM32F103RET6B-PA11-Pad44)") (class "Default")
      (node (ref "STM32F103RET6") (pin "44") (pinfunction "PA11_44") (pintype "bidirectional"))
    )
    (net (code "78") (name "unconnected-(STM32F103RET6F-PC13-Pad2)") (class "Default")
      (node (ref "STM32F103RET6") (pin "2") (pinfunction "PC13_2") (pintype "bidirectional"))
    )
    (net (code "79") (name "unconnected-(STM32F103RET6F-PC14-Pad3)") (class "Default")
      (node (ref "STM32F103RET6") (pin "3") (pinfunction "PC14_3") (pintype "bidirectional"))
    )
    (net (code "80") (name "unconnected-(STM32F103RET6F-PC15-Pad4)") (class "Default")
      (node (ref "STM32F103RET6") (pin "4") (pinfunction "PC15_4") (pintype "bidirectional"))
    )
    (net (code "81") (name "unconnected-(STM32F103RET6G-PC0-Pad8)") (class "Default")
      (node (ref "STM32F103RET6") (pin "8") (pinfunction "PC0_8") (pintype "bidirectional"))
    )
    (net (code "82") (name "unconnected-(STM32F103RET6G-PC3-Pad11)") (class "Default")
      (node (ref "STM32F103RET6") (pin "11") (pinfunction "PC3_11") (pintype "bidirectional"))
    )
    (net (code "83") (name "unconnected-(STM32F103RET6G-PC5-Pad25)") (class "Default")
      (node (ref "STM32F103RET6") (pin "25") (pinfunction "PC5_25") (pintype "bidirectional"))
    )
    (net (code "84") (name "unconnected-(STM32F103RET6H-PD2-Pad54)") (class "Default")
      (node (ref "STM32F103RET6") (pin "54") (pinfunction "PD2_54") (pintype "bidirectional"))
    )
    (net (code "85") (name "unconnected-(U$3-GPIO2-Pad8)") (class "Default")
      (node (ref "U$3") (pin "8") (pinfunction "GPIO2_8") (pintype "bidirectional"))
    )
    (net (code "86") (name "unconnected-(U1-CLKOUT-Pad22)") (class "Default")
      (node (ref "U1") (pin "22") (pinfunction "CLKOUT_22") (pintype "bidirectional"))
    )
  )
)
